# doogie_top_board.net
KiCad netlist of a schematic drawn in EAGLE
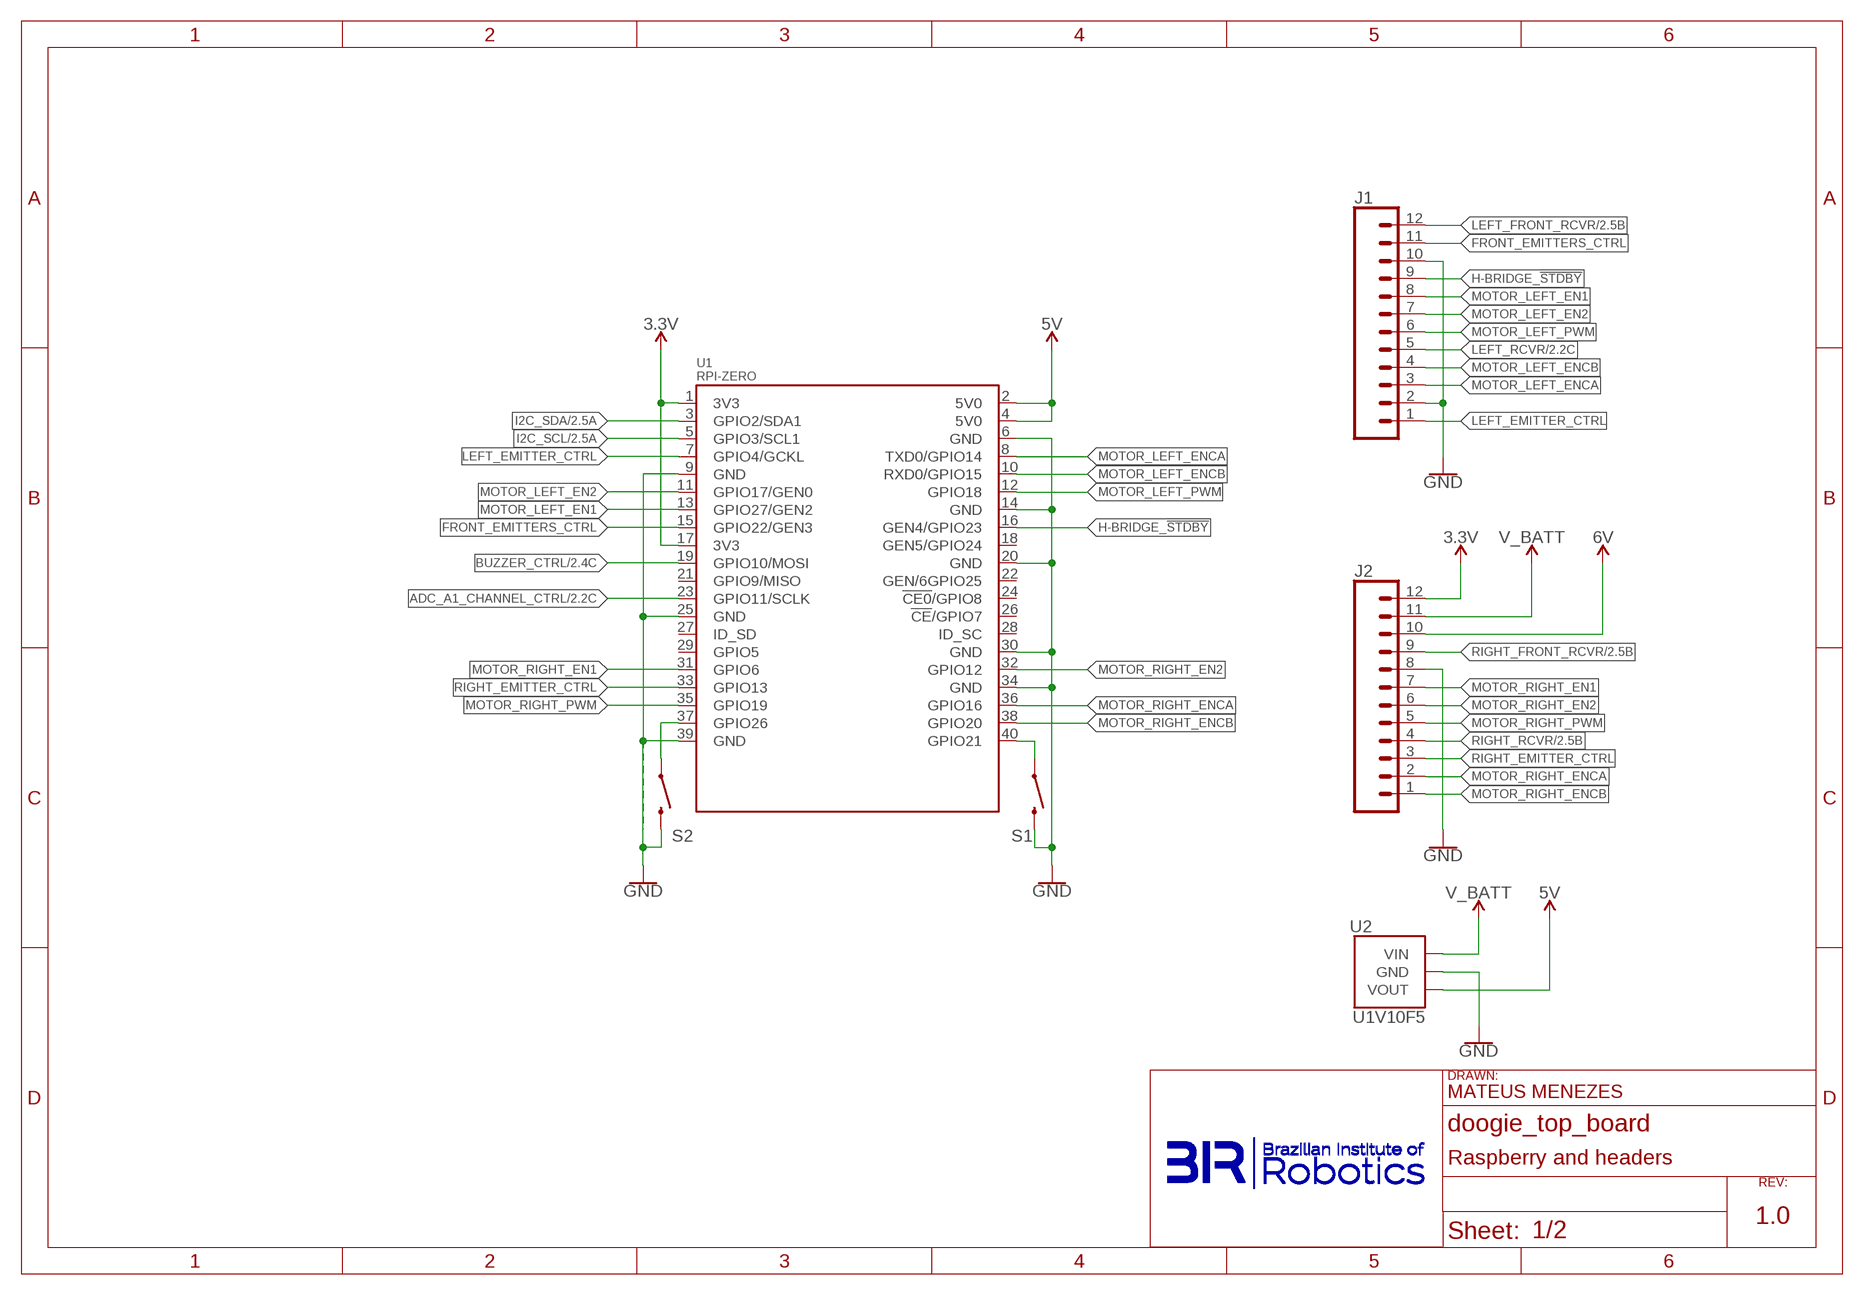
[diagram p0: schematic, sheet 1]
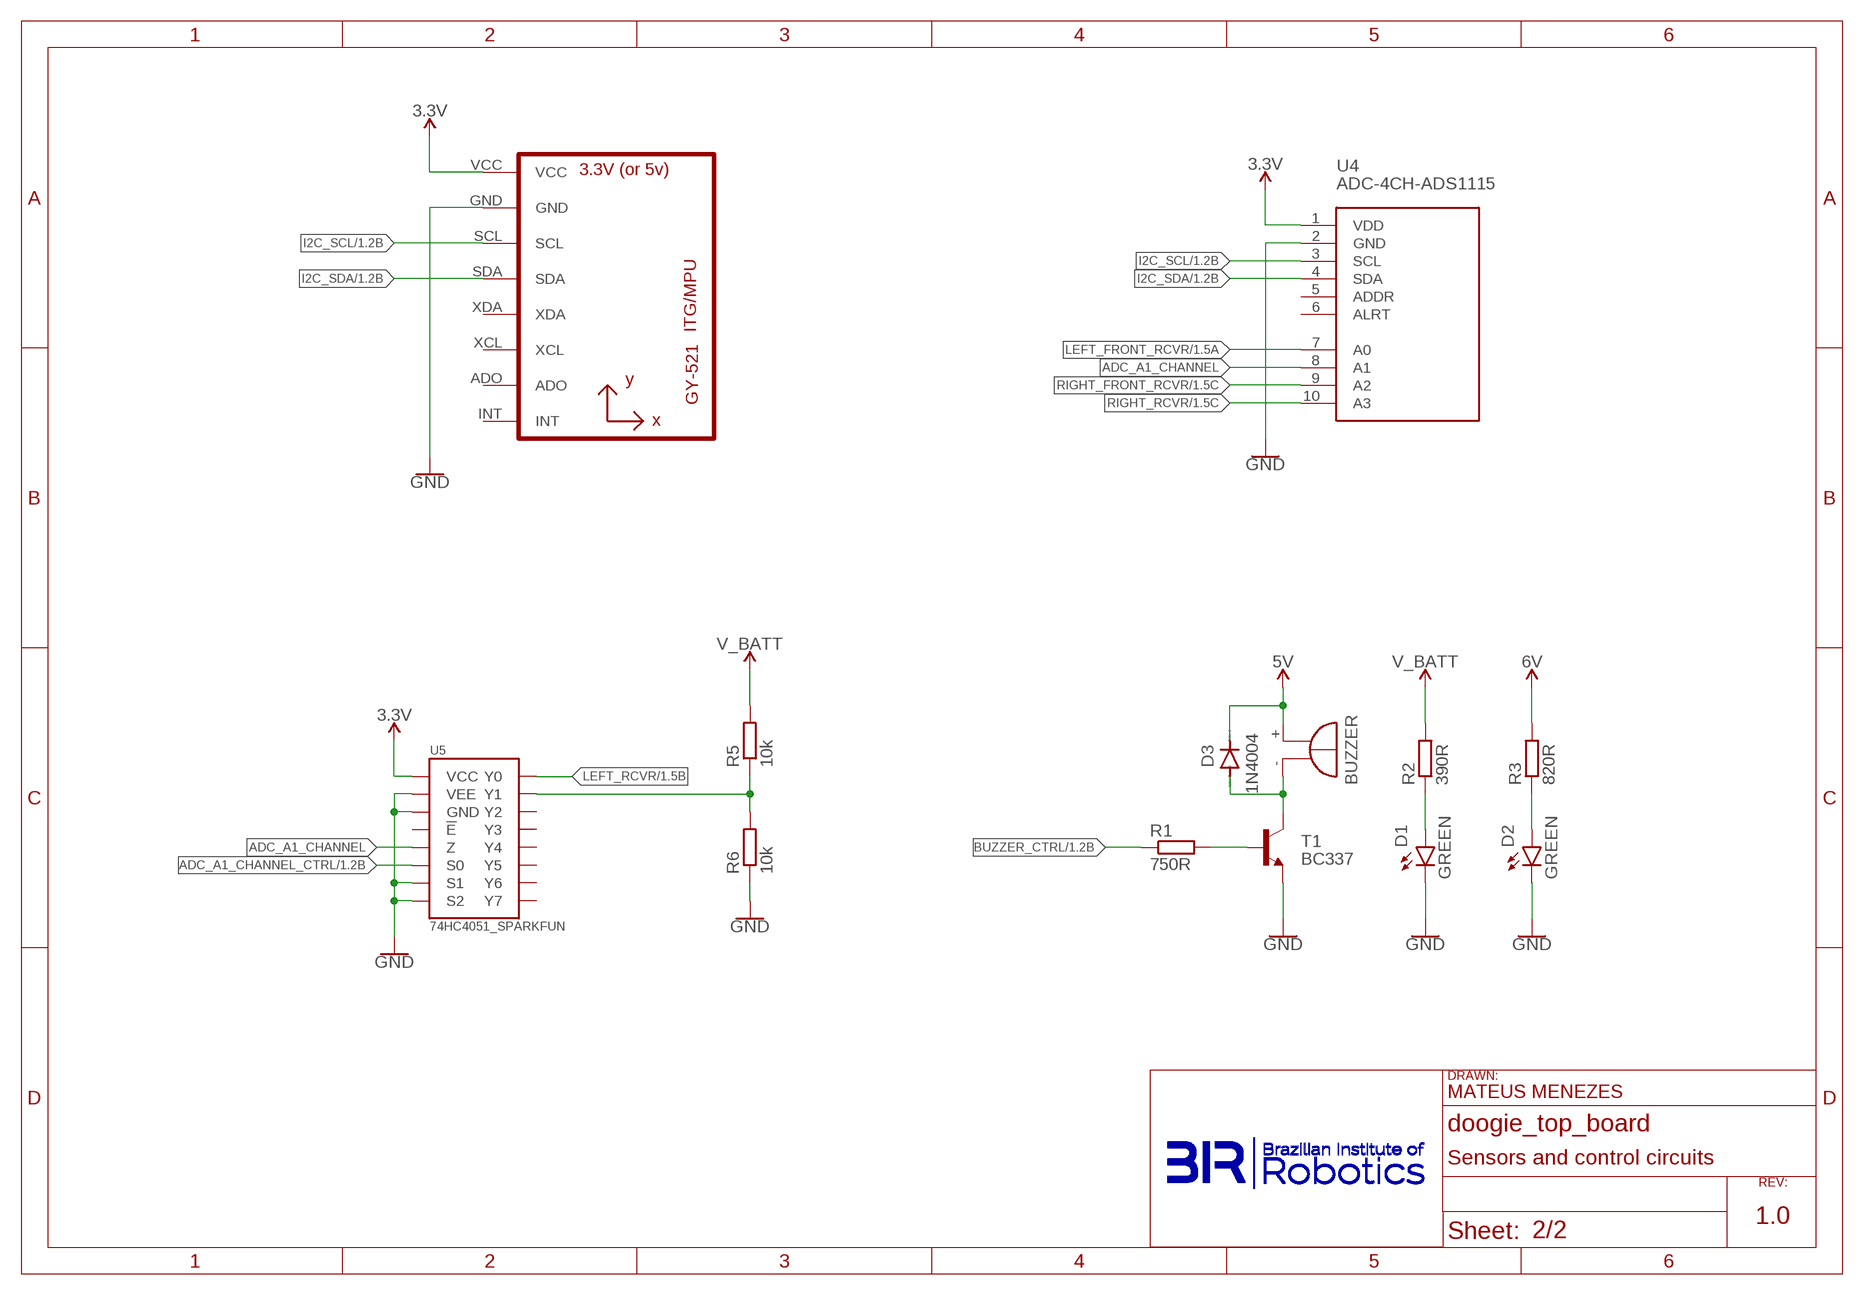
[diagram p1: schematic, sheet 2]

(export (version "E")
  (design (tool "Eeschema 10.0.6"))
  (components
    (comp (ref "J1")
      (value "CONN_12")
      (footprint "eagle-import:1X12")
      (libsource (lib "eagle-import") (part "CONN_12"))
    )
    (comp (ref "J2")
      (value "CONN_12")
      (footprint "eagle-import:1X12")
      (libsource (lib "eagle-import") (part "CONN_12"))
    )
    (comp (ref "S1")
      (value "MOMENTARY-SWITCH-SPST-PTH-6.0MM")
      (footprint "eagle-import:TACTILE_SWITCH_PTH_6.0MM")
      (libsource (lib "eagle-import") (part "MOMENTARY-SWITCH-SPST-PTH-6.0MM"))
    )
    (comp (ref "S2")
      (value "MOMENTARY-SWITCH-SPST-PTH-6.0MM")
      (footprint "eagle-import:TACTILE_SWITCH_PTH_6.0MM")
      (libsource (lib "eagle-import") (part "MOMENTARY-SWITCH-SPST-PTH-6.0MM"))
    )
    (comp (ref "U1")
      (value "RPI-ZERO")
      (footprint "eagle-import:RASPBERRYPI_BASTELSTUBE_V13_RASPI_BOARD_B+_FULL")
      (libsource (lib "eagle-import") (part "RPI-ZERO"))
    )
    (comp (ref "U2")
      (value "U1V10F5")
      (footprint "eagle-import:U1V10F5")
      (libsource (lib "eagle-import") (part "U1V10F5"))
    )
    (comp (ref "BUZZER")
      (value "F/TMB")
      (footprint "eagle-import:F_TMB")
      (libsource (lib "eagle-import") (part "F/TMB"))
    )
    (comp (ref "D1")
      (value "GREEN")
      (footprint "eagle-import:LED_3MM")
      (libsource (lib "eagle-import") (part "LED3MM"))
    )
    (comp (ref "D2")
      (value "GREEN")
      (footprint "eagle-import:LED_3MM")
      (libsource (lib "eagle-import") (part "LED3MM"))
    )
    (comp (ref "D3")
      (value "1N4004")
      (footprint "eagle-import:DO41-10")
      (libsource (lib "eagle-import") (part "1N4004"))
    )
    (comp (ref "R1")
      (value "750R")
      (footprint "eagle-import:0204_7")
      (libsource (lib "eagle-import") (part "R-EU_0204/7"))
    )
    (comp (ref "R2")
      (value "390R")
      (footprint "eagle-import:0204_7")
      (libsource (lib "eagle-import") (part "R-EU_0204/7"))
    )
    (comp (ref "R3")
      (value "820R")
      (footprint "eagle-import:0204_7")
      (libsource (lib "eagle-import") (part "R-EU_0204/7"))
    )
    (comp (ref "R5")
      (value "10k")
      (footprint "eagle-import:0204_7")
      (libsource (lib "eagle-import") (part "R-EU_0204/7"))
    )
    (comp (ref "R6")
      (value "10k")
      (footprint "eagle-import:0204_7")
      (libsource (lib "eagle-import") (part "R-EU_0204/7"))
    )
    (comp (ref "T1")
      (value "BC337")
      (footprint "eagle-import:TO92")
      (libsource (lib "eagle-import") (part "BC337"))
    )
    (comp (ref "U3")
      (value "GY-521MPU6050")
      (footprint "eagle-import:GY-521")
      (libsource (lib "eagle-import") (part "GY-521MPU6050"))
    )
    (comp (ref "U4")
      (value "ADC-4CH-ADS1115")
      (footprint "eagle-import:ADC-4CH-ADS1115")
      (libsource (lib "eagle-import") (part "ADC-4CH-ADS1115"))
    )
    (comp (ref "U5")
      (value "74HC4051_SPARKFUN")
      (footprint "eagle-import:74HC4051_SPARKFUN")
      (libsource (lib "eagle-import") (part "74HC4051_SPARKFUN"))
    )
  )
  (nets
    (net (code "1") (name "3.3V") (class "Default")
      (node (ref "J2") (pin "12") (pinfunction "12_12") (pintype "passive"))
      (node (ref "U1") (pin "1") (pinfunction "3V3_1") (pintype "power_in"))
      (node (ref "U1") (pin "17") (pinfunction "3V3_17") (pintype "power_in"))
      (node (ref "U3") (pin "VCC") (pinfunction "VCC_VCC") (pintype "bidirectional"))
      (node (ref "U4") (pin "1") (pinfunction "VDD_1") (pintype "power_in"))
      (node (ref "U5") (pin "VCC") (pinfunction "VCC_VCC") (pintype "power_in"))
      (node (ref "U5") (pin "VCC@1") (pinfunction "VCC_VCC@1") (pintype "power_in"))
    )
    (net (code "2") (name "5V") (class "Default")
      (node (ref "BUZZER") (pin "+") (pinfunction "+_+") (pintype "passive"))
      (node (ref "D3") (pin "C") (pinfunction "C_C") (pintype "passive"))
      (node (ref "U1") (pin "2") (pinfunction "5V0_2") (pintype "power_in"))
      (node (ref "U1") (pin "4") (pinfunction "5V0_4") (pintype "power_in"))
      (node (ref "U2") (pin "VOUT") (pinfunction "VOUT_VOUT") (pintype "power_in"))
    )
    (net (code "3") (name "ADC_A1_CHANNEL") (class "Default")
      (node (ref "U4") (pin "8") (pinfunction "A1_8") (pintype "input"))
      (node (ref "U5") (pin "Z") (pinfunction "Z_Z") (pintype "bidirectional"))
    )
    (net (code "4") (name "ADC_A1_CHANNEL_CTRL") (class "Default")
      (node (ref "U1") (pin "23") (pinfunction "GPIO11/SCLK_23") (pintype "bidirectional"))
      (node (ref "U5") (pin "S0") (pinfunction "S0_S0") (pintype "input"))
    )
    (net (code "5") (name "BUZZER_CTRL") (class "Default")
      (node (ref "R1") (pin "1") (pinfunction "1_1") (pintype "passive"))
      (node (ref "U1") (pin "19") (pinfunction "GPIO10/MOSI_19") (pintype "bidirectional"))
    )
    (net (code "6") (name "FRONT_EMITTERS_CTRL") (class "Default")
      (node (ref "J1") (pin "11") (pinfunction "11_11") (pintype "passive"))
      (node (ref "U1") (pin "15") (pinfunction "GPIO22/GEN3_15") (pintype "bidirectional"))
    )
    (net (code "7") (name "GND") (class "Default")
      (node (ref "D1") (pin "K") (pinfunction "C_K") (pintype "passive"))
      (node (ref "D2") (pin "K") (pinfunction "C_K") (pintype "passive"))
      (node (ref "J1") (pin "10") (pinfunction "10_10") (pintype "passive"))
      (node (ref "J1") (pin "2") (pinfunction "2_2") (pintype "passive"))
      (node (ref "J2") (pin "8") (pinfunction "8_8") (pintype "passive"))
      (node (ref "R6") (pin "1") (pinfunction "1_1") (pintype "passive"))
      (node (ref "S1") (pin "3") (pinfunction "2_3") (pintype "passive"))
      (node (ref "S2") (pin "3") (pinfunction "2_3") (pintype "passive"))
      (node (ref "T1") (pin "1") (pinfunction "E_1") (pintype "passive"))
      (node (ref "U1") (pin "14") (pinfunction "GND_14") (pintype "power_in"))
      (node (ref "U1") (pin "20") (pinfunction "GND_20") (pintype "power_in"))
      (node (ref "U1") (pin "25") (pinfunction "GND_25") (pintype "power_in"))
      (node (ref "U1") (pin "30") (pinfunction "GND_30") (pintype "power_in"))
      (node (ref "U1") (pin "34") (pinfunction "GND_34") (pintype "power_in"))
      (node (ref "U1") (pin "39") (pinfunction "GND_39") (pintype "power_in"))
      (node (ref "U1") (pin "6") (pinfunction "GND_6") (pintype "power_in"))
      (node (ref "U1") (pin "9") (pinfunction "GND_9") (pintype "power_in"))
      (node (ref "U2") (pin "GND") (pinfunction "GND_GND") (pintype "power_in"))
      (node (ref "U3") (pin "GND") (pinfunction "GND_GND") (pintype "bidirectional"))
      (node (ref "U4") (pin "2") (pinfunction "GND_2") (pintype "power_in"))
      (node (ref "U5") (pin "GND") (pinfunction "GND_GND") (pintype "power_in"))
      (node (ref "U5") (pin "GND@1") (pinfunction "GND_GND@1") (pintype "power_in"))
      (node (ref "U5") (pin "S1") (pinfunction "S1_S1") (pintype "input"))
      (node (ref "U5") (pin "S2") (pinfunction "S2_S2") (pintype "input"))
      (node (ref "U5") (pin "VEE") (pinfunction "VEE_VEE") (pintype "power_in"))
      (node (ref "U5") (pin "VEE@1") (pinfunction "VEE_VEE@1") (pintype "power_in"))
    )
    (net (code "8") (name "H-BRIDGE_~{STDBY}") (class "Default")
      (node (ref "J1") (pin "9") (pinfunction "9_9") (pintype "passive"))
      (node (ref "U1") (pin "16") (pinfunction "GEN4/GPIO23_16") (pintype "bidirectional"))
    )
    (net (code "9") (name "I2C_SCL") (class "Default")
      (node (ref "U1") (pin "5") (pinfunction "GPIO3/SCL1_5") (pintype "bidirectional"))
      (node (ref "U3") (pin "SCL") (pinfunction "SCL_SCL") (pintype "bidirectional"))
      (node (ref "U4") (pin "3") (pinfunction "SCL_3") (pintype "bidirectional"))
    )
    (net (code "10") (name "I2C_SDA") (class "Default")
      (node (ref "U1") (pin "3") (pinfunction "GPIO2/SDA1_3") (pintype "bidirectional"))
      (node (ref "U3") (pin "SDA") (pinfunction "SDA_SDA") (pintype "bidirectional"))
      (node (ref "U4") (pin "4") (pinfunction "SDA_4") (pintype "bidirectional"))
    )
    (net (code "11") (name "LEFT_EMITTER_CTRL") (class "Default")
      (node (ref "J1") (pin "1") (pinfunction "1_1") (pintype "passive"))
      (node (ref "U1") (pin "7") (pinfunction "GPIO4/GCKL_7") (pintype "bidirectional"))
    )
    (net (code "12") (name "LEFT_FRONT_RCVR") (class "Default")
      (node (ref "J1") (pin "12") (pinfunction "12_12") (pintype "passive"))
      (node (ref "U4") (pin "7") (pinfunction "A0_7") (pintype "input"))
    )
    (net (code "13") (name "LEFT_RCVR") (class "Default")
      (node (ref "J1") (pin "5") (pinfunction "5_5") (pintype "passive"))
      (node (ref "U5") (pin "Y0") (pinfunction "Y0_Y0") (pintype "bidirectional"))
    )
    (net (code "14") (name "MOTOR_LEFT_EN1") (class "Default")
      (node (ref "J1") (pin "8") (pinfunction "8_8") (pintype "passive"))
      (node (ref "U1") (pin "13") (pinfunction "GPIO27/GEN2_13") (pintype "bidirectional"))
    )
    (net (code "15") (name "MOTOR_LEFT_EN2") (class "Default")
      (node (ref "J1") (pin "7") (pinfunction "7_7") (pintype "passive"))
      (node (ref "U1") (pin "11") (pinfunction "GPIO17/GEN0_11") (pintype "bidirectional"))
    )
    (net (code "16") (name "MOTOR_LEFT_ENCA") (class "Default")
      (node (ref "J1") (pin "3") (pinfunction "3_3") (pintype "passive"))
      (node (ref "U1") (pin "8") (pinfunction "TXD0/GPIO14_8") (pintype "bidirectional"))
    )
    (net (code "17") (name "MOTOR_LEFT_ENCB") (class "Default")
      (node (ref "J1") (pin "4") (pinfunction "4_4") (pintype "passive"))
      (node (ref "U1") (pin "10") (pinfunction "RXD0/GPIO15_10") (pintype "bidirectional"))
    )
    (net (code "18") (name "MOTOR_LEFT_PWM") (class "Default")
      (node (ref "J1") (pin "6") (pinfunction "6_6") (pintype "passive"))
      (node (ref "U1") (pin "12") (pinfunction "GPIO18_12") (pintype "bidirectional"))
    )
    (net (code "19") (name "MOTOR_RIGHT_EN1") (class "Default")
      (node (ref "J2") (pin "7") (pinfunction "7_7") (pintype "passive"))
      (node (ref "U1") (pin "31") (pinfunction "GPIO6_31") (pintype "bidirectional"))
    )
    (net (code "20") (name "MOTOR_RIGHT_EN2") (class "Default")
      (node (ref "J2") (pin "6") (pinfunction "6_6") (pintype "passive"))
      (node (ref "U1") (pin "32") (pinfunction "GPIO12_32") (pintype "bidirectional"))
    )
    (net (code "21") (name "MOTOR_RIGHT_ENCA") (class "Default")
      (node (ref "J2") (pin "2") (pinfunction "2_2") (pintype "passive"))
      (node (ref "U1") (pin "36") (pinfunction "GPIO16_36") (pintype "bidirectional"))
    )
    (net (code "22") (name "MOTOR_RIGHT_ENCB") (class "Default")
      (node (ref "J2") (pin "1") (pinfunction "1_1") (pintype "passive"))
      (node (ref "U1") (pin "38") (pinfunction "GPIO20_38") (pintype "bidirectional"))
    )
    (net (code "23") (name "MOTOR_RIGHT_PWM") (class "Default")
      (node (ref "J2") (pin "5") (pinfunction "5_5") (pintype "passive"))
      (node (ref "U1") (pin "35") (pinfunction "GPIO19_35") (pintype "bidirectional"))
    )
    (net (code "24") (name "Net-(D1-PadA)") (class "Default")
      (node (ref "D1") (pin "A") (pinfunction "A_A") (pintype "passive"))
      (node (ref "R2") (pin "1") (pinfunction "1_1") (pintype "passive"))
    )
    (net (code "25") (name "Net-(D2-PadA)") (class "Default")
      (node (ref "D2") (pin "A") (pinfunction "A_A") (pintype "passive"))
      (node (ref "R3") (pin "1") (pinfunction "1_1") (pintype "passive"))
    )
    (net (code "26") (name "Net-(R5-Pad1)") (class "Default")
      (node (ref "R5") (pin "1") (pinfunction "1_1") (pintype "passive"))
      (node (ref "R6") (pin "2") (pinfunction "2_2") (pintype "passive"))
      (node (ref "U5") (pin "Y1") (pinfunction "Y1_Y1") (pintype "bidirectional"))
    )
    (net (code "27") (name "Net-(T1-B)") (class "Default")
      (node (ref "R1") (pin "2") (pinfunction "2_2") (pintype "passive"))
      (node (ref "T1") (pin "2") (pinfunction "B_2") (pintype "passive"))
    )
    (net (code "28") (name "Net-(T1-C)") (class "Default")
      (node (ref "BUZZER") (pin "-") (pinfunction "-_-") (pintype "passive"))
      (node (ref "D3") (pin "A") (pinfunction "A_A") (pintype "passive"))
      (node (ref "T1") (pin "3") (pinfunction "C_3") (pintype "passive"))
    )
    (net (code "29") (name "Net-(U1-GPIO21)") (class "Default")
      (node (ref "S1") (pin "1") (pinfunction "1_1") (pintype "passive"))
      (node (ref "U1") (pin "40") (pinfunction "GPIO21_40") (pintype "bidirectional"))
    )
    (net (code "30") (name "Net-(U1-GPIO26)") (class "Default")
      (node (ref "S2") (pin "1") (pinfunction "1_1") (pintype "passive"))
      (node (ref "U1") (pin "37") (pinfunction "GPIO26_37") (pintype "bidirectional"))
    )
    (net (code "31") (name "RIGHT_EMITTER_CTRL") (class "Default")
      (node (ref "J2") (pin "3") (pinfunction "3_3") (pintype "passive"))
      (node (ref "U1") (pin "33") (pinfunction "GPIO13_33") (pintype "bidirectional"))
    )
    (net (code "32") (name "RIGHT_FRONT_RCVR") (class "Default")
      (node (ref "J2") (pin "9") (pinfunction "9_9") (pintype "passive"))
      (node (ref "U4") (pin "9") (pinfunction "A2_9") (pintype "input"))
    )
    (net (code "33") (name "RIGHT_RCVR") (class "Default")
      (node (ref "J2") (pin "4") (pinfunction "4_4") (pintype "passive"))
      (node (ref "U4") (pin "10") (pinfunction "A3_10") (pintype "input"))
    )
    (net (code "34") (name "VOUT") (class "Default")
      (node (ref "J2") (pin "10") (pinfunction "10_10") (pintype "passive"))
      (node (ref "R3") (pin "2") (pinfunction "2_2") (pintype "passive"))
    )
    (net (code "35") (name "V_BATT") (class "Default")
      (node (ref "J2") (pin "11") (pinfunction "11_11") (pintype "passive"))
      (node (ref "R2") (pin "2") (pinfunction "2_2") (pintype "passive"))
      (node (ref "R5") (pin "2") (pinfunction "2_2") (pintype "passive"))
      (node (ref "U2") (pin "VIN") (pinfunction "VIN_VIN") (pintype "power_in"))
    )
    (net (code "36") (name "unconnected-(U1-GEN5{slash}GPIO24-Pad18)") (class "Default")
      (node (ref "U1") (pin "18") (pinfunction "GEN5/GPIO24_18") (pintype "bidirectional"))
    )
    (net (code "37") (name "unconnected-(U1-GEN{slash}6GPIO25-Pad22)") (class "Default")
      (node (ref "U1") (pin "22") (pinfunction "GEN/6GPIO25_22") (pintype "bidirectional"))
    )
    (net (code "38") (name "unconnected-(U1-GPIO5-Pad29)") (class "Default")
      (node (ref "U1") (pin "29") (pinfunction "GPIO5_29") (pintype "bidirectional"))
    )
    (net (code "39") (name "unconnected-(U1-GPIO9{slash}MISO-Pad21)") (class "Default")
      (node (ref "U1") (pin "21") (pinfunction "GPIO9/MISO_21") (pintype "bidirectional"))
    )
    (net (code "40") (name "unconnected-(U1-ID_SC-Pad28)") (class "Default")
      (node (ref "U1") (pin "28") (pinfunction "ID_SC_28") (pintype "bidirectional"))
    )
    (net (code "41") (name "unconnected-(U1-ID_SD-Pad27)") (class "Default")
      (node (ref "U1") (pin "27") (pinfunction "ID_SD_27") (pintype "bidirectional"))
    )
    (net (code "42") (name "unconnected-(U1-~{CE0}{slash}GPIO8-Pad24)") (class "Default")
      (node (ref "U1") (pin "24") (pinfunction "~{CE0}/GPIO8_24") (pintype "bidirectional"))
    )
    (net (code "43") (name "unconnected-(U1-~{CE}{slash}GPIO7-Pad26)") (class "Default")
      (node (ref "U1") (pin "26") (pinfunction "~{CE}/GPIO7_26") (pintype "bidirectional"))
    )
    (net (code "44") (name "unconnected-(U3-PadADO)") (class "Default")
      (node (ref "U3") (pin "ADO") (pinfunction "ADO_ADO") (pintype "bidirectional"))
    )
    (net (code "45") (name "unconnected-(U3-PadINT)") (class "Default")
      (node (ref "U3") (pin "INT") (pinfunction "INT_INT") (pintype "bidirectional"))
    )
    (net (code "46") (name "unconnected-(U3-PadXCL)") (class "Default")
      (node (ref "U3") (pin "XCL") (pinfunction "XCL_XCL") (pintype "bidirectional"))
    )
    (net (code "47") (name "unconnected-(U3-PadXDA)") (class "Default")
      (node (ref "U3") (pin "XDA") (pinfunction "XDA_XDA") (pintype "bidirectional"))
    )
    (net (code "48") (name "unconnected-(U4-ADDR-Pad5)") (class "Default")
      (node (ref "U4") (pin "5") (pinfunction "ADDR_5") (pintype "bidirectional"))
    )
    (net (code "49") (name "unconnected-(U4-ALRT-Pad6)") (class "Default")
      (node (ref "U4") (pin "6") (pinfunction "ALRT_6") (pintype "bidirectional"))
    )
    (net (code "50") (name "unconnected-(U5-PadY2)") (class "Default")
      (node (ref "U5") (pin "Y2") (pinfunction "Y2_Y2") (pintype "bidirectional"))
    )
    (net (code "51") (name "unconnected-(U5-PadY3)") (class "Default")
      (node (ref "U5") (pin "Y3") (pinfunction "Y3_Y3") (pintype "bidirectional"))
    )
    (net (code "52") (name "unconnected-(U5-PadY4)") (class "Default")
      (node (ref "U5") (pin "Y4") (pinfunction "Y4_Y4") (pintype "bidirectional"))
    )
    (net (code "53") (name "unconnected-(U5-PadY5)") (class "Default")
      (node (ref "U5") (pin "Y5") (pinfunction "Y5_Y5") (pintype "bidirectional"))
    )
    (net (code "54") (name "unconnected-(U5-PadY6)") (class "Default")
      (node (ref "U5") (pin "Y6") (pinfunction "Y6_Y6") (pintype "bidirectional"))
    )
    (net (code "55") (name "unconnected-(U5-PadY7)") (class "Default")
      (node (ref "U5") (pin "Y7") (pinfunction "Y7_Y7") (pintype "bidirectional"))
    )
    (net (code "56") (name "unconnected-(U5-~{E}-Pad!E)") (class "Default")
      (node (ref "U5") (pin "!E") (pinfunction "~{E}_!E") (pintype "input"))
    )
  )
)
